# picstick_uart_rpi4_vdiv.net
KiCad netlist of a schematic drawn in EAGLE
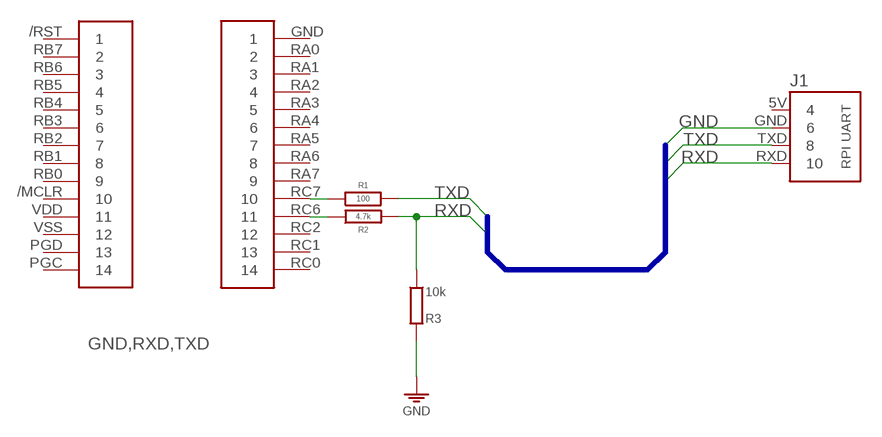
[diagram p0: schematic, sheet 1]

(export (version "E")
  (design (tool "Eeschema 10.0.6"))
  (components
    (comp (ref "J1")
      (value "RPI-UART-RPI4")
      (footprint "eagle-import:RPI-UART")
      (libsource (lib "eagle-import") (part "RPI-UART-RPI4"))
    )
    (comp (ref "J2")
      (value "PICSTICK")
      (footprint "eagle-import:PICSTICK_ALT")
      (libsource (lib "eagle-import") (part "PICSTICK"))
    )
    (comp (ref "R1")
      (value "100")
      (footprint "eagle-import:0204_12")
      (libsource (lib "eagle-import") (part "R-H0204/12"))
    )
    (comp (ref "R2")
      (value "4.7k")
      (footprint "eagle-import:0204_12")
      (libsource (lib "eagle-import") (part "R-H0204/12"))
    )
    (comp (ref "R3")
      (value "10k")
      (footprint "eagle-import:0204_12-V")
      (libsource (lib "eagle-import") (part "R0204/12-V"))
    )
  )
  (nets
    (net (code "1") (name "/RXD") (class "Default")
      (node (ref "J1") (pin "RXD") (pinfunction "10_RXD") (pintype "passive"))
      (node (ref "R2") (pin "2") (pinfunction "2_2") (pintype "passive"))
      (node (ref "R3") (pin "2") (pinfunction "1_2") (pintype "passive"))
    )
    (net (code "2") (name "/TXD") (class "Default")
      (node (ref "J1") (pin "TXD") (pinfunction "8_TXD") (pintype "passive"))
      (node (ref "R1") (pin "2") (pinfunction "2_2") (pintype "passive"))
    )
    (net (code "4") (name "GND") (class "Default")
      (node (ref "J1") (pin "GND") (pinfunction "6_GND") (pintype "passive"))
      (node (ref "R3") (pin "1") (pinfunction "2_1") (pintype "passive"))
    )
    (net (code "5") (name "Net-(J2B-10)") (class "Default")
      (node (ref "J2") (pin "RC7") (pinfunction "10_RC7") (pintype "bidirectional"))
      (node (ref "R1") (pin "1") (pinfunction "1_1") (pintype "passive"))
    )
    (net (code "6") (name "Net-(J2B-11)") (class "Default")
      (node (ref "J2") (pin "RC6") (pinfunction "11_RC6") (pintype "bidirectional"))
      (node (ref "R2") (pin "1") (pinfunction "1_1") (pintype "passive"))
    )
    (net (code "7") (name "unconnected-(J1-4-Pad5V)") (class "Default")
      (node (ref "J1") (pin "5V") (pinfunction "4_5V") (pintype "passive"))
    )
    (net (code "8") (name "unconnected-(J2A-1-Pad{slash}RST)") (class "Default")
      (node (ref "J2") (pin "/RST") (pinfunction "1_/RST") (pintype "bidirectional"))
    )
    (net (code "9") (name "unconnected-(J2A-2-PadRB7)") (class "Default")
      (node (ref "J2") (pin "RB7") (pinfunction "2_RB7") (pintype "bidirectional"))
    )
    (net (code "10") (name "unconnected-(J2A-3-PadRB6)") (class "Default")
      (node (ref "J2") (pin "RB6") (pinfunction "3_RB6") (pintype "bidirectional"))
    )
    (net (code "11") (name "unconnected-(J2A-4-PadRB5)") (class "Default")
      (node (ref "J2") (pin "RB5") (pinfunction "4_RB5") (pintype "bidirectional"))
    )
    (net (code "12") (name "unconnected-(J2A-5-PadRB4)") (class "Default")
      (node (ref "J2") (pin "RB4") (pinfunction "5_RB4") (pintype "bidirectional"))
    )
    (net (code "13") (name "unconnected-(J2A-6-PadRB3)") (class "Default")
      (node (ref "J2") (pin "RB3") (pinfunction "6_RB3") (pintype "bidirectional"))
    )
    (net (code "14") (name "unconnected-(J2A-7-PadRB2)") (class "Default")
      (node (ref "J2") (pin "RB2") (pinfunction "7_RB2") (pintype "bidirectional"))
    )
    (net (code "15") (name "unconnected-(J2A-8-PadRB1)") (class "Default")
      (node (ref "J2") (pin "RB1") (pinfunction "8_RB1") (pintype "bidirectional"))
    )
    (net (code "16") (name "unconnected-(J2A-9-PadRB0)") (class "Default")
      (node (ref "J2") (pin "RB0") (pinfunction "9_RB0") (pintype "bidirectional"))
    )
    (net (code "17") (name "unconnected-(J2A-10-Pad{slash}MCLR)") (class "Default")
      (node (ref "J2") (pin "/MCLR") (pinfunction "10_/MCLR") (pintype "bidirectional"))
    )
    (net (code "18") (name "unconnected-(J2A-11-PadVDD)") (class "Default")
      (node (ref "J2") (pin "VDD") (pinfunction "11_VDD") (pintype "bidirectional"))
    )
    (net (code "19") (name "unconnected-(J2A-12-PadVSS)") (class "Default")
      (node (ref "J2") (pin "VSS") (pinfunction "12_VSS") (pintype "bidirectional"))
    )
    (net (code "20") (name "unconnected-(J2A-13-PadPGD)") (class "Default")
      (node (ref "J2") (pin "PGD") (pinfunction "13_PGD") (pintype "bidirectional"))
    )
    (net (code "21") (name "unconnected-(J2A-14-PadPGC)") (class "Default")
      (node (ref "J2") (pin "PGC") (pinfunction "14_PGC") (pintype "bidirectional"))
    )
    (net (code "22") (name "unconnected-(J2B-1-PadGND)") (class "Default")
      (node (ref "J2") (pin "GND") (pinfunction "1_GND") (pintype "bidirectional"))
    )
    (net (code "23") (name "unconnected-(J2B-2-PadRA0)") (class "Default")
      (node (ref "J2") (pin "RA0") (pinfunction "2_RA0") (pintype "bidirectional"))
    )
    (net (code "24") (name "unconnected-(J2B-3-PadRA1)") (class "Default")
      (node (ref "J2") (pin "RA1") (pinfunction "3_RA1") (pintype "bidirectional"))
    )
    (net (code "25") (name "unconnected-(J2B-4-PadRA2)") (class "Default")
      (node (ref "J2") (pin "RA2") (pinfunction "4_RA2") (pintype "bidirectional"))
    )
    (net (code "26") (name "unconnected-(J2B-5-PadRA3)") (class "Default")
      (node (ref "J2") (pin "RA3") (pinfunction "5_RA3") (pintype "bidirectional"))
    )
    (net (code "27") (name "unconnected-(J2B-6-PadRA4)") (class "Default")
      (node (ref "J2") (pin "RA4") (pinfunction "6_RA4") (pintype "bidirectional"))
    )
    (net (code "28") (name "unconnected-(J2B-7-PadRA5)") (class "Default")
      (node (ref "J2") (pin "RA5") (pinfunction "7_RA5") (pintype "bidirectional"))
    )
    (net (code "29") (name "unconnected-(J2B-8-PadRA6)") (class "Default")
      (node (ref "J2") (pin "RA6") (pinfunction "8_RA6") (pintype "bidirectional"))
    )
    (net (code "30") (name "unconnected-(J2B-9-PadRA7)") (class "Default")
      (node (ref "J2") (pin "RA7") (pinfunction "9_RA7") (pintype "bidirectional"))
    )
    (net (code "31") (name "unconnected-(J2B-12-PadRC2)") (class "Default")
      (node (ref "J2") (pin "RC2") (pinfunction "12_RC2") (pintype "bidirectional"))
    )
    (net (code "32") (name "unconnected-(J2B-13-PadRC1)") (class "Default")
      (node (ref "J2") (pin "RC1") (pinfunction "13_RC1") (pintype "bidirectional"))
    )
    (net (code "33") (name "unconnected-(J2B-14-PadRC0)") (class "Default")
      (node (ref "J2") (pin "RC0") (pinfunction "14_RC0") (pintype "bidirectional"))
    )
  )
)
